# beaglebone.net
KiCad netlist of a schematic drawn in Altium Designer
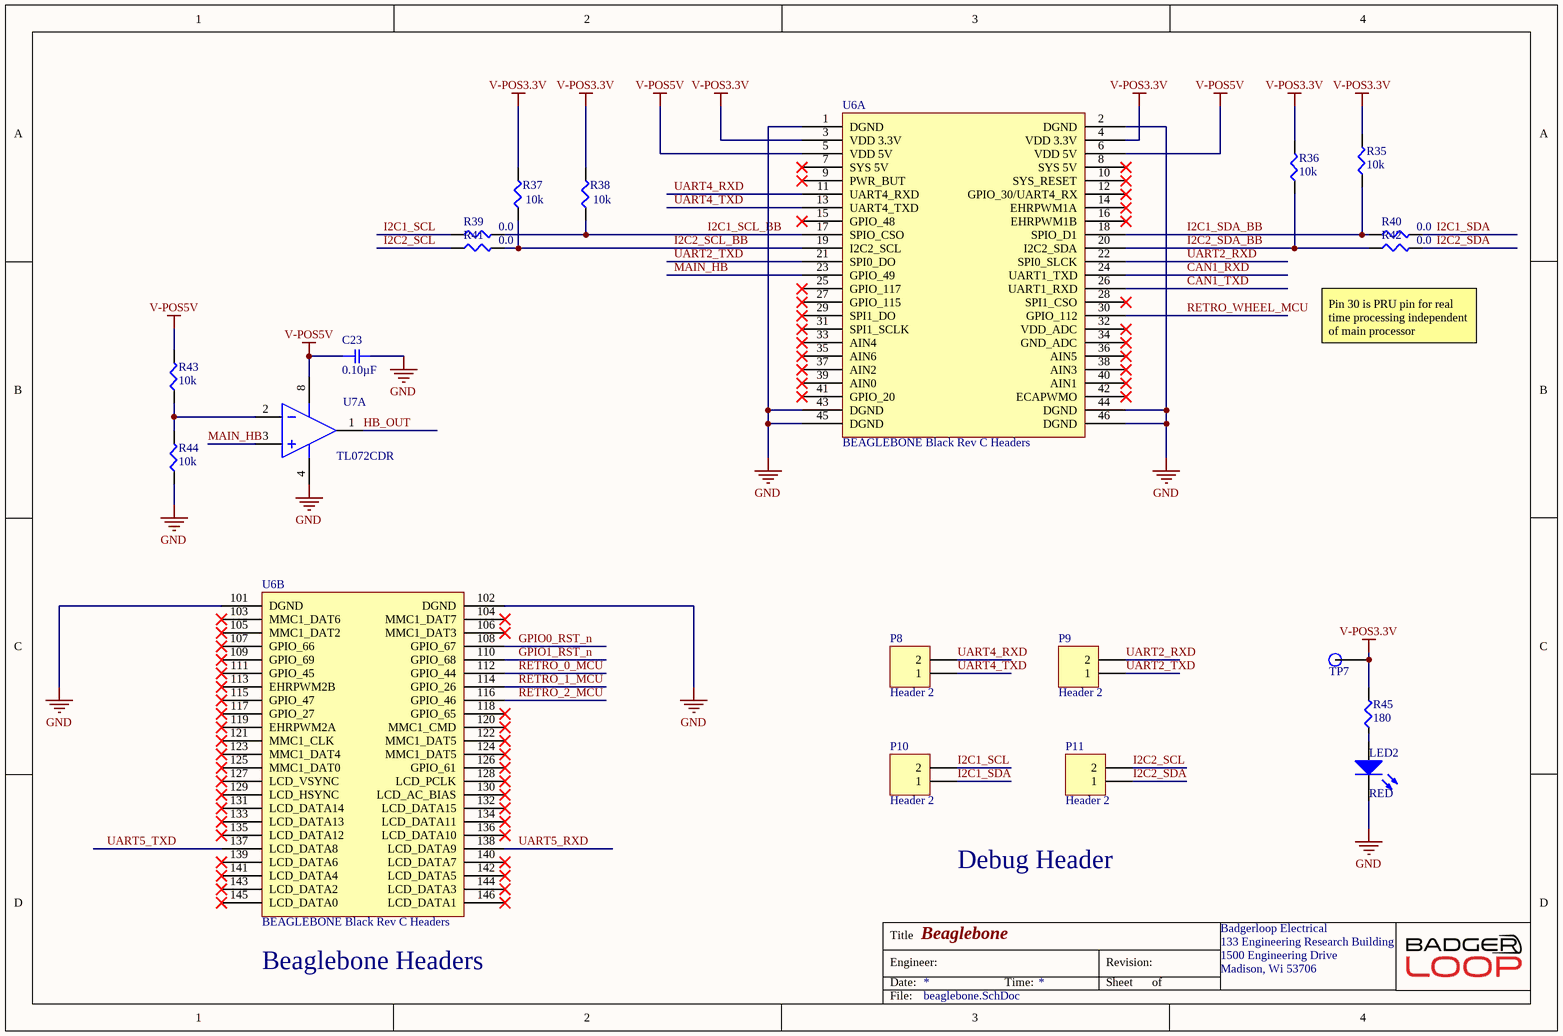
[diagram p0: beaglebone.SchDoc]

(export (version "E")
  (design (tool "Eeschema 10.0.6"))
  (components
    (comp (ref "C23")
      (value "0.10µF")
      (footprint "SMD-0805C")
      (description "CAP CER 0.1UF 10V U2J 0805")
      (fields
        (field (name "DIGI-KEY PART NUMBER") "490-11592-1-ND")
        (field (name "PART NUMBER") "GRM21B7U1A104JA01L")
      )
      (libsource (lib "capacitors") (part "GRM21B7U1A104JA01L"))
    )
    (comp (ref "LED2")
      (value "RED")
      (footprint "LED 0603 RED")
      (description "Red 631nm LED Indication - Discrete 2V 0603 (1608 Metric)")
      (fields (field (name "MANUFACTURER") "Lite-On Inc."))
      (libsource (lib "misc") (part "LED RED 0603"))
    )
    (comp (ref "P8")
      (value "Header 2")
      (footprint "Pin Header 1x2 TH Pitch 2.54mm")
      (description "Header, 2-Pin")
      (fields (field (name "PUBLISHER") "Altium Limited"))
      (libsource (lib "connector") (part "Header 2"))
    )
    (comp (ref "P9")
      (value "Header 2")
      (footprint "Pin Header 1x2 TH Pitch 2.54mm")
      (description "Header, 2-Pin")
      (fields (field (name "PUBLISHER") "Altium Limited"))
      (libsource (lib "connector") (part "Header 2"))
    )
    (comp (ref "P10")
      (value "Header 2")
      (footprint "Pin Header 1x2 TH Pitch 2.54mm")
      (description "Header, 2-Pin")
      (fields (field (name "PUBLISHER") "Altium Limited"))
      (libsource (lib "connector") (part "Header 2"))
    )
    (comp (ref "P11")
      (value "Header 2")
      (footprint "Pin Header 1x2 TH Pitch 2.54mm")
      (description "Header, 2-Pin")
      (fields (field (name "PUBLISHER") "Altium Limited"))
      (libsource (lib "connector") (part "Header 2"))
    )
    (comp (ref "R35")
      (value "10k")
      (footprint "SMD-0805-RES")
      (description "RES SMD 10K OHM 5% 1/8W 0805")
      (fields (field (name "PART NUMBER") "ERJ-6GEYJ103V") (field (name "DIGI-KEY PART NUMBER") "P10KACT-ND"))
      (libsource (lib "resistors") (part "ERJ-6GEYJ103V"))
    )
    (comp (ref "R36")
      (value "10k")
      (footprint "SMD-0805-RES")
      (description "RES SMD 10K OHM 5% 1/8W 0805")
      (fields (field (name "PART NUMBER") "ERJ-6GEYJ103V") (field (name "DIGI-KEY PART NUMBER") "P10KACT-ND"))
      (libsource (lib "resistors") (part "ERJ-6GEYJ103V"))
    )
    (comp (ref "R37")
      (value "10k")
      (footprint "SMD-0805-RES")
      (description "RES SMD 10K OHM 5% 1/8W 0805")
      (fields (field (name "PART NUMBER") "ERJ-6GEYJ103V") (field (name "DIGI-KEY PART NUMBER") "P10KACT-ND"))
      (libsource (lib "resistors") (part "ERJ-6GEYJ103V"))
    )
    (comp (ref "R38")
      (value "10k")
      (footprint "SMD-0805-RES")
      (description "RES SMD 10K OHM 5% 1/8W 0805")
      (fields (field (name "PART NUMBER") "ERJ-6GEYJ103V") (field (name "DIGI-KEY PART NUMBER") "P10KACT-ND"))
      (libsource (lib "resistors") (part "ERJ-6GEYJ103V"))
    )
    (comp (ref "R39")
      (value "0.0")
      (footprint "SMD-1206-RES")
      (description "RES SMD 0.0 OHM JUMPER 1/4W 1206")
      (fields (field (name "PART NUMBER") "ERJ-8GEY0R00V") (field (name "DIGI-KEY PART NUMBER") "P0.0ECT-ND"))
      (libsource (lib "resistors") (part "ERJ-8GEY0R00V"))
    )
    (comp (ref "R40")
      (value "0.0")
      (footprint "SMD-1206-RES")
      (description "RES SMD 0.0 OHM JUMPER 1/4W 1206")
      (fields (field (name "PART NUMBER") "ERJ-8GEY0R00V") (field (name "DIGI-KEY PART NUMBER") "P0.0ECT-ND"))
      (libsource (lib "resistors") (part "ERJ-8GEY0R00V"))
    )
    (comp (ref "R41")
      (value "0.0")
      (footprint "SMD-1206-RES")
      (description "RES SMD 0.0 OHM JUMPER 1/4W 1206")
      (fields (field (name "PART NUMBER") "ERJ-8GEY0R00V") (field (name "DIGI-KEY PART NUMBER") "P0.0ECT-ND"))
      (libsource (lib "resistors") (part "ERJ-8GEY0R00V"))
    )
    (comp (ref "R42")
      (value "0.0")
      (footprint "SMD-1206-RES")
      (description "RES SMD 0.0 OHM JUMPER 1/4W 1206")
      (fields (field (name "PART NUMBER") "ERJ-8GEY0R00V") (field (name "DIGI-KEY PART NUMBER") "P0.0ECT-ND"))
      (libsource (lib "resistors") (part "ERJ-8GEY0R00V"))
    )
    (comp (ref "R43")
      (value "10k")
      (footprint "SMD-0805-RES")
      (description "RES SMD 10K OHM 5% 1/2W 0805")
      (fields (field (name "PART NUMBER") "ERJ-P06J103V") (field (name "DIGI-KEY PART NUMBER") "P10KADCT-ND"))
      (libsource (lib "resistors") (part "ERJ-P06J103V"))
    )
    (comp (ref "R44")
      (value "10k")
      (footprint "SMD-0805-RES")
      (description "RES SMD 10K OHM 5% 1/2W 0805")
      (fields (field (name "PART NUMBER") "ERJ-P06J103V") (field (name "DIGI-KEY PART NUMBER") "P10KADCT-ND"))
      (libsource (lib "resistors") (part "ERJ-P06J103V"))
    )
    (comp (ref "R45")
      (value "180")
      (footprint "SMD-0805-RES")
      (description "RES SMD 180 OHM 1% 1/8W 0805")
      (fields (field (name "PART NUMBER") "ERJ-6ENF1800V") (field (name "DIGI-KEY PART NUMBER") "P180CCT-ND"))
      (libsource (lib "resistors") (part "ERJ-6ENF1800V"))
    )
    (comp (ref "TP7")
      (value "TP")
      (footprint "Test Point")
      (description "SMD TEST POINT")
      (libsource (lib "misc") (part "TP"))
    )
    (comp (ref "U6")
      (value "BEAGLEBONE Black Rev C Headers")
      (footprint "Beaglebone_Topside")
      (description "Beaglebone Black Rev C Header")
      (libsource (lib "temp") (part "Beaglebone"))
    )
    (comp (ref "U7")
      (value "TL072CDR")
      (footprint "SOP127P600X175-8N")
      (description "IC OPAMP JFET 3MHZ 8SOIC")
      (fields (field (name "MANUFACTURER") "Texas Instruments"))
      (libsource (lib "ic") (part "TL072CDR"))
    )
  )
  (nets
    (net (code "1") (name "/CAN1_RXD") (class "Default")
      (node (ref "U6") (pin "24") (pinfunction "UART1_TXD_24") (pintype "passive"))
    )
    (net (code "2") (name "/CAN1_TXD") (class "Default")
      (node (ref "U6") (pin "26") (pinfunction "UART1_RXD_26") (pintype "passive"))
    )
    (net (code "3") (name "/GPIO0_RST_n") (class "Default")
      (node (ref "U6") (pin "108") (pinfunction "GPIO_67_108") (pintype "passive"))
    )
    (net (code "4") (name "/GPIO1_RST_n") (class "Default")
      (node (ref "U6") (pin "110") (pinfunction "GPIO_68_110") (pintype "passive"))
    )
    (net (code "5") (name "/HB_OUT") (class "Default")
      (node (ref "U7") (pin "1") (pinfunction "OUT_1") (pintype "passive"))
    )
    (net (code "6") (name "/I2C1_SCL") (class "Default")
      (node (ref "P10") (pin "2") (pinfunction "2_2") (pintype "passive"))
      (node (ref "R39") (pin "1") (pinfunction "1_1") (pintype "passive"))
    )
    (net (code "7") (name "/I2C1_SCL_BB") (class "Default")
      (node (ref "R38") (pin "1") (pinfunction "1_1") (pintype "passive"))
      (node (ref "R39") (pin "2") (pinfunction "2_2") (pintype "passive"))
      (node (ref "U6") (pin "17") (pinfunction "SPIO_CSO_17") (pintype "passive"))
    )
    (net (code "8") (name "/I2C1_SDA") (class "Default")
      (node (ref "P10") (pin "1") (pinfunction "1_1") (pintype "passive"))
      (node (ref "R40") (pin "2") (pinfunction "2_2") (pintype "passive"))
    )
    (net (code "9") (name "/I2C1_SDA_BB") (class "Default")
      (node (ref "R35") (pin "1") (pinfunction "1_1") (pintype "passive"))
      (node (ref "R40") (pin "1") (pinfunction "1_1") (pintype "passive"))
      (node (ref "U6") (pin "18") (pinfunction "SPIO_D1_18") (pintype "passive"))
    )
    (net (code "10") (name "/I2C2_SCL") (class "Default")
      (node (ref "P11") (pin "2") (pinfunction "2_2") (pintype "passive"))
      (node (ref "R41") (pin "1") (pinfunction "1_1") (pintype "passive"))
    )
    (net (code "11") (name "/I2C2_SCL_BB") (class "Default")
      (node (ref "R37") (pin "1") (pinfunction "1_1") (pintype "passive"))
      (node (ref "R41") (pin "2") (pinfunction "2_2") (pintype "passive"))
      (node (ref "U6") (pin "19") (pinfunction "I2C2_SCL_19") (pintype "passive"))
    )
    (net (code "12") (name "/I2C2_SDA") (class "Default")
      (node (ref "P11") (pin "1") (pinfunction "1_1") (pintype "passive"))
      (node (ref "R42") (pin "2") (pinfunction "2_2") (pintype "passive"))
    )
    (net (code "13") (name "/I2C2_SDA_BB") (class "Default")
      (node (ref "R36") (pin "1") (pinfunction "1_1") (pintype "passive"))
      (node (ref "R42") (pin "1") (pinfunction "1_1") (pintype "passive"))
      (node (ref "U6") (pin "20") (pinfunction "I2C2_SDA_20") (pintype "passive"))
    )
    (net (code "14") (name "/MAIN_HB") (class "Default")
      (node (ref "U6") (pin "23") (pinfunction "GPIO_49_23") (pintype "passive"))
      (node (ref "U7") (pin "3") (pinfunction "IN+_3") (pintype "passive"))
    )
    (net (code "15") (name "/RETRO_0_MCU") (class "Default")
      (node (ref "U6") (pin "112") (pinfunction "GPIO_44_112") (pintype "passive"))
    )
    (net (code "16") (name "/RETRO_1_MCU") (class "Default")
      (node (ref "U6") (pin "114") (pinfunction "GPIO_26_114") (pintype "passive"))
    )
    (net (code "17") (name "/RETRO_2_MCU") (class "Default")
      (node (ref "U6") (pin "116") (pinfunction "GPIO_46_116") (pintype "passive"))
    )
    (net (code "18") (name "/RETRO_WHEEL_MCU") (class "Default")
      (node (ref "U6") (pin "30") (pinfunction "GPIO_112_30") (pintype "passive"))
    )
    (net (code "19") (name "/UART2_RXD") (class "Default")
      (node (ref "P9") (pin "2") (pinfunction "2_2") (pintype "passive"))
      (node (ref "U6") (pin "22") (pinfunction "SPI0_SLCK_22") (pintype "passive"))
    )
    (net (code "20") (name "/UART2_TXD") (class "Default")
      (node (ref "P9") (pin "1") (pinfunction "1_1") (pintype "passive"))
      (node (ref "U6") (pin "21") (pinfunction "SPI0_DO_21") (pintype "passive"))
    )
    (net (code "21") (name "/UART4_RXD") (class "Default")
      (node (ref "P8") (pin "2") (pinfunction "2_2") (pintype "passive"))
      (node (ref "U6") (pin "11") (pinfunction "UART4_RXD_11") (pintype "passive"))
    )
    (net (code "22") (name "/UART4_TXD") (class "Default")
      (node (ref "P8") (pin "1") (pinfunction "1_1") (pintype "passive"))
      (node (ref "U6") (pin "13") (pinfunction "UART4_TXD_13") (pintype "passive"))
    )
    (net (code "23") (name "/UART5_RXD") (class "Default")
      (node (ref "U6") (pin "138") (pinfunction "LCD_DATA9_138") (pintype "passive"))
    )
    (net (code "24") (name "/UART5_TXD") (class "Default")
      (node (ref "U6") (pin "137") (pinfunction "LCD_DATA8_137") (pintype "passive"))
    )
    (net (code "25") (name "GND") (class "Default")
      (node (ref "C23") (pin "2") (pinfunction "2_2") (pintype "passive"))
      (node (ref "LED2") (pin "2") (pinfunction "K_2") (pintype "passive"))
      (node (ref "R44") (pin "1") (pinfunction "1_1") (pintype "passive"))
      (node (ref "U6") (pin "1") (pinfunction "DGND_1") (pintype "passive"))
      (node (ref "U6") (pin "101") (pinfunction "DGND_101") (pintype "passive"))
      (node (ref "U6") (pin "102") (pinfunction "DGND_102") (pintype "passive"))
      (node (ref "U6") (pin "2") (pinfunction "DGND_2") (pintype "passive"))
      (node (ref "U6") (pin "43") (pinfunction "DGND_43") (pintype "passive"))
      (node (ref "U6") (pin "44") (pinfunction "DGND_44") (pintype "passive"))
      (node (ref "U6") (pin "45") (pinfunction "DGND_45") (pintype "passive"))
      (node (ref "U6") (pin "46") (pinfunction "DGND_46") (pintype "passive"))
      (node (ref "U7") (pin "4") (pinfunction "V-_4") (pintype "power_in"))
    )
    (net (code "26") (name "Net-(LED2-A)") (class "Default")
      (node (ref "LED2") (pin "1") (pinfunction "A_1") (pintype "passive"))
      (node (ref "R45") (pin "1") (pinfunction "1_1") (pintype "passive"))
    )
    (net (code "27") (name "Net-(U7A-IN-)") (class "Default")
      (node (ref "R43") (pin "1") (pinfunction "1_1") (pintype "passive"))
      (node (ref "R44") (pin "2") (pinfunction "2_2") (pintype "passive"))
      (node (ref "U7") (pin "2") (pinfunction "IN-_2") (pintype "passive"))
    )
    (net (code "28") (name "V-POS3.3V") (class "Default")
      (node (ref "R35") (pin "2") (pinfunction "2_2") (pintype "passive"))
      (node (ref "R36") (pin "2") (pinfunction "2_2") (pintype "passive"))
      (node (ref "R37") (pin "2") (pinfunction "2_2") (pintype "passive"))
      (node (ref "R38") (pin "2") (pinfunction "2_2") (pintype "passive"))
      (node (ref "R45") (pin "2") (pinfunction "2_2") (pintype "passive"))
      (node (ref "TP7") (pin "1") (pinfunction "1_1") (pintype "passive"))
      (node (ref "U6") (pin "3") (pinfunction "VDD_3.3V_3") (pintype "passive"))
      (node (ref "U6") (pin "4") (pinfunction "VDD_3.3V_4") (pintype "passive"))
    )
    (net (code "29") (name "V-POS5V") (class "Default")
      (node (ref "C23") (pin "1") (pinfunction "1_1") (pintype "passive"))
      (node (ref "R43") (pin "2") (pinfunction "2_2") (pintype "passive"))
      (node (ref "U6") (pin "5") (pinfunction "VDD_5V_5") (pintype "passive"))
      (node (ref "U6") (pin "6") (pinfunction "VDD_5V_6") (pintype "passive"))
      (node (ref "U7") (pin "8") (pinfunction "V+_8") (pintype "power_in"))
    )
    (net (code "30") (name "unconnected-(U6A-AIN0-Pad39)") (class "Default")
      (node (ref "U6") (pin "39") (pinfunction "AIN0_39") (pintype "passive+no_connect"))
    )
    (net (code "31") (name "unconnected-(U6A-AIN1-Pad40)") (class "Default")
      (node (ref "U6") (pin "40") (pinfunction "AIN1_40") (pintype "passive+no_connect"))
    )
    (net (code "32") (name "unconnected-(U6A-AIN2-Pad37)") (class "Default")
      (node (ref "U6") (pin "37") (pinfunction "AIN2_37") (pintype "passive+no_connect"))
    )
    (net (code "33") (name "unconnected-(U6A-AIN3-Pad38)") (class "Default")
      (node (ref "U6") (pin "38") (pinfunction "AIN3_38") (pintype "passive+no_connect"))
    )
    (net (code "34") (name "unconnected-(U6A-AIN4-Pad33)") (class "Default")
      (node (ref "U6") (pin "33") (pinfunction "AIN4_33") (pintype "passive+no_connect"))
    )
    (net (code "35") (name "unconnected-(U6A-AIN5-Pad36)") (class "Default")
      (node (ref "U6") (pin "36") (pinfunction "AIN5_36") (pintype "passive+no_connect"))
    )
    (net (code "36") (name "unconnected-(U6A-AIN6-Pad35)") (class "Default")
      (node (ref "U6") (pin "35") (pinfunction "AIN6_35") (pintype "passive+no_connect"))
    )
    (net (code "37") (name "unconnected-(U6A-ECAPWMO-Pad42)") (class "Default")
      (node (ref "U6") (pin "42") (pinfunction "ECAPWMO_42") (pintype "passive+no_connect"))
    )
    (net (code "38") (name "unconnected-(U6A-EHRPWM1A-Pad14)") (class "Default")
      (node (ref "U6") (pin "14") (pinfunction "EHRPWM1A_14") (pintype "passive+no_connect"))
    )
    (net (code "39") (name "unconnected-(U6A-EHRPWM1B-Pad16)") (class "Default")
      (node (ref "U6") (pin "16") (pinfunction "EHRPWM1B_16") (pintype "passive+no_connect"))
    )
    (net (code "40") (name "unconnected-(U6A-GND_ADC-Pad34)") (class "Default")
      (node (ref "U6") (pin "34") (pinfunction "GND_ADC_34") (pintype "passive+no_connect"))
    )
    (net (code "41") (name "unconnected-(U6A-GPIO_20-Pad41)") (class "Default")
      (node (ref "U6") (pin "41") (pinfunction "GPIO_20_41") (pintype "passive+no_connect"))
    )
    (net (code "42") (name "unconnected-(U6A-GPIO_30{slash}UART4_RX-Pad12)") (class "Default")
      (node (ref "U6") (pin "12") (pinfunction "GPIO_30/UART4_RX_12") (pintype "passive+no_connect"))
    )
    (net (code "43") (name "unconnected-(U6A-GPIO_48-Pad15)") (class "Default")
      (node (ref "U6") (pin "15") (pinfunction "GPIO_48_15") (pintype "passive+no_connect"))
    )
    (net (code "44") (name "unconnected-(U6A-GPIO_115-Pad27)") (class "Default")
      (node (ref "U6") (pin "27") (pinfunction "GPIO_115_27") (pintype "passive+no_connect"))
    )
    (net (code "45") (name "unconnected-(U6A-GPIO_117-Pad25)") (class "Default")
      (node (ref "U6") (pin "25") (pinfunction "GPIO_117_25") (pintype "passive+no_connect"))
    )
    (net (code "46") (name "unconnected-(U6A-PWR_BUT-Pad9)") (class "Default")
      (node (ref "U6") (pin "9") (pinfunction "PWR_BUT_9") (pintype "passive+no_connect"))
    )
    (net (code "47") (name "unconnected-(U6A-SPI1_CSO-Pad28)") (class "Default")
      (node (ref "U6") (pin "28") (pinfunction "SPI1_CSO_28") (pintype "passive+no_connect"))
    )
    (net (code "48") (name "unconnected-(U6A-SPI1_DO-Pad29)") (class "Default")
      (node (ref "U6") (pin "29") (pinfunction "SPI1_DO_29") (pintype "passive+no_connect"))
    )
    (net (code "49") (name "unconnected-(U6A-SPI1_SCLK-Pad31)") (class "Default")
      (node (ref "U6") (pin "31") (pinfunction "SPI1_SCLK_31") (pintype "passive+no_connect"))
    )
    (net (code "50") (name "unconnected-(U6A-SYS_5V-Pad7)") (class "Default")
      (node (ref "U6") (pin "7") (pinfunction "SYS_5V_7") (pintype "passive+no_connect"))
    )
    (net (code "51") (name "unconnected-(U6A-SYS_5V-Pad8)") (class "Default")
      (node (ref "U6") (pin "8") (pinfunction "SYS_5V_8") (pintype "passive+no_connect"))
    )
    (net (code "52") (name "unconnected-(U6A-SYS_RESET-Pad10)") (class "Default")
      (node (ref "U6") (pin "10") (pinfunction "SYS_RESET_10") (pintype "passive+no_connect"))
    )
    (net (code "53") (name "unconnected-(U6A-VDD_ADC-Pad32)") (class "Default")
      (node (ref "U6") (pin "32") (pinfunction "VDD_ADC_32") (pintype "passive+no_connect"))
    )
    (net (code "54") (name "unconnected-(U6B-EHRPWM2A-Pad119)") (class "Default")
      (node (ref "U6") (pin "119") (pinfunction "EHRPWM2A_119") (pintype "passive+no_connect"))
    )
    (net (code "55") (name "unconnected-(U6B-EHRPWM2B-Pad113)") (class "Default")
      (node (ref "U6") (pin "113") (pinfunction "EHRPWM2B_113") (pintype "passive+no_connect"))
    )
    (net (code "56") (name "unconnected-(U6B-GPIO_27-Pad117)") (class "Default")
      (node (ref "U6") (pin "117") (pinfunction "GPIO_27_117") (pintype "passive+no_connect"))
    )
    (net (code "57") (name "unconnected-(U6B-GPIO_45-Pad111)") (class "Default")
      (node (ref "U6") (pin "111") (pinfunction "GPIO_45_111") (pintype "passive+no_connect"))
    )
    (net (code "58") (name "unconnected-(U6B-GPIO_47-Pad115)") (class "Default")
      (node (ref "U6") (pin "115") (pinfunction "GPIO_47_115") (pintype "passive+no_connect"))
    )
    (net (code "59") (name "unconnected-(U6B-GPIO_61-Pad126)") (class "Default")
      (node (ref "U6") (pin "126") (pinfunction "GPIO_61_126") (pintype "passive+no_connect"))
    )
    (net (code "60") (name "unconnected-(U6B-GPIO_65-Pad118)") (class "Default")
      (node (ref "U6") (pin "118") (pinfunction "GPIO_65_118") (pintype "passive+no_connect"))
    )
    (net (code "61") (name "unconnected-(U6B-GPIO_66-Pad107)") (class "Default")
      (node (ref "U6") (pin "107") (pinfunction "GPIO_66_107") (pintype "passive+no_connect"))
    )
    (net (code "62") (name "unconnected-(U6B-GPIO_69-Pad109)") (class "Default")
      (node (ref "U6") (pin "109") (pinfunction "GPIO_69_109") (pintype "passive+no_connect"))
    )
    (net (code "63") (name "unconnected-(U6B-LCD_AC_BIAS-Pad130)") (class "Default")
      (node (ref "U6") (pin "130") (pinfunction "LCD_AC_BIAS_130") (pintype "passive+no_connect"))
    )
    (net (code "64") (name "unconnected-(U6B-LCD_DATA0-Pad145)") (class "Default")
      (node (ref "U6") (pin "145") (pinfunction "LCD_DATA0_145") (pintype "passive+no_connect"))
    )
    (net (code "65") (name "unconnected-(U6B-LCD_DATA1-Pad146)") (class "Default")
      (node (ref "U6") (pin "146") (pinfunction "LCD_DATA1_146") (pintype "passive+no_connect"))
    )
    (net (code "66") (name "unconnected-(U6B-LCD_DATA2-Pad143)") (class "Default")
      (node (ref "U6") (pin "143") (pinfunction "LCD_DATA2_143") (pintype "passive+no_connect"))
    )
    (net (code "67") (name "unconnected-(U6B-LCD_DATA3-Pad144)") (class "Default")
      (node (ref "U6") (pin "144") (pinfunction "LCD_DATA3_144") (pintype "passive+no_connect"))
    )
    (net (code "68") (name "unconnected-(U6B-LCD_DATA4-Pad141)") (class "Default")
      (node (ref "U6") (pin "141") (pinfunction "LCD_DATA4_141") (pintype "passive+no_connect"))
    )
    (net (code "69") (name "unconnected-(U6B-LCD_DATA5-Pad142)") (class "Default")
      (node (ref "U6") (pin "142") (pinfunction "LCD_DATA5_142") (pintype "passive+no_connect"))
    )
    (net (code "70") (name "unconnected-(U6B-LCD_DATA6-Pad139)") (class "Default")
      (node (ref "U6") (pin "139") (pinfunction "LCD_DATA6_139") (pintype "passive+no_connect"))
    )
    (net (code "71") (name "unconnected-(U6B-LCD_DATA7-Pad140)") (class "Default")
      (node (ref "U6") (pin "140") (pinfunction "LCD_DATA7_140") (pintype "passive+no_connect"))
    )
    (net (code "72") (name "unconnected-(U6B-LCD_DATA10-Pad136)") (class "Default")
      (node (ref "U6") (pin "136") (pinfunction "LCD_DATA10_136") (pintype "passive+no_connect"))
    )
    (net (code "73") (name "unconnected-(U6B-LCD_DATA11-Pad134)") (class "Default")
      (node (ref "U6") (pin "134") (pinfunction "LCD_DATA11_134") (pintype "passive+no_connect"))
    )
    (net (code "74") (name "unconnected-(U6B-LCD_DATA12-Pad135)") (class "Default")
      (node (ref "U6") (pin "135") (pinfunction "LCD_DATA12_135") (pintype "passive+no_connect"))
    )
    (net (code "75") (name "unconnected-(U6B-LCD_DATA13-Pad133)") (class "Default")
      (node (ref "U6") (pin "133") (pinfunction "LCD_DATA13_133") (pintype "passive+no_connect"))
    )
    (net (code "76") (name "unconnected-(U6B-LCD_DATA14-Pad131)") (class "Default")
      (node (ref "U6") (pin "131") (pinfunction "LCD_DATA14_131") (pintype "passive+no_connect"))
    )
    (net (code "77") (name "unconnected-(U6B-LCD_DATA15-Pad132)") (class "Default")
      (node (ref "U6") (pin "132") (pinfunction "LCD_DATA15_132") (pintype "passive+no_connect"))
    )
    (net (code "78") (name "unconnected-(U6B-LCD_HSYNC-Pad129)") (class "Default")
      (node (ref "U6") (pin "129") (pinfunction "LCD_HSYNC_129") (pintype "passive+no_connect"))
    )
    (net (code "79") (name "unconnected-(U6B-LCD_PCLK-Pad128)") (class "Default")
      (node (ref "U6") (pin "128") (pinfunction "LCD_PCLK_128") (pintype "passive+no_connect"))
    )
    (net (code "80") (name "unconnected-(U6B-LCD_VSYNC-Pad127)") (class "Default")
      (node (ref "U6") (pin "127") (pinfunction "LCD_VSYNC_127") (pintype "passive+no_connect"))
    )
    (net (code "81") (name "unconnected-(U6B-MMC1_CLK-Pad121)") (class "Default")
      (node (ref "U6") (pin "121") (pinfunction "MMC1_CLK_121") (pintype "passive+no_connect"))
    )
    (net (code "82") (name "unconnected-(U6B-MMC1_CMD-Pad120)") (class "Default")
      (node (ref "U6") (pin "120") (pinfunction "MMC1_CMD_120") (pintype "passive+no_connect"))
    )
    (net (code "83") (name "unconnected-(U6B-MMC1_DAT0-Pad125)") (class "Default")
      (node (ref "U6") (pin "125") (pinfunction "MMC1_DAT0_125") (pintype "passive+no_connect"))
    )
    (net (code "84") (name "unconnected-(U6B-MMC1_DAT2-Pad105)") (class "Default")
      (node (ref "U6") (pin "105") (pinfunction "MMC1_DAT2_105") (pintype "passive+no_connect"))
    )
    (net (code "85") (name "unconnected-(U6B-MMC1_DAT3-Pad106)") (class "Default")
      (node (ref "U6") (pin "106") (pinfunction "MMC1_DAT3_106") (pintype "passive+no_connect"))
    )
    (net (code "86") (name "unconnected-(U6B-MMC1_DAT4-Pad123)") (class "Default")
      (node (ref "U6") (pin "123") (pinfunction "MMC1_DAT4_123") (pintype "passive+no_connect"))
    )
    (net (code "87") (name "unconnected-(U6B-MMC1_DAT5-Pad122)") (class "Default")
      (node (ref "U6") (pin "122") (pinfunction "MMC1_DAT5_122") (pintype "passive+no_connect"))
    )
    (net (code "88") (name "unconnected-(U6B-MMC1_DAT5-Pad124)") (class "Default")
      (node (ref "U6") (pin "124") (pinfunction "MMC1_DAT5_124") (pintype "passive+no_connect"))
    )
    (net (code "89") (name "unconnected-(U6B-MMC1_DAT6-Pad103)") (class "Default")
      (node (ref "U6") (pin "103") (pinfunction "MMC1_DAT6_103") (pintype "passive+no_connect"))
    )
    (net (code "90") (name "unconnected-(U6B-MMC1_DAT7-Pad104)") (class "Default")
      (node (ref "U6") (pin "104") (pinfunction "MMC1_DAT7_104") (pintype "passive+no_connect"))
    )
  )
)
